# System.net
KiCad netlist of a schematic drawn in Altium Designer
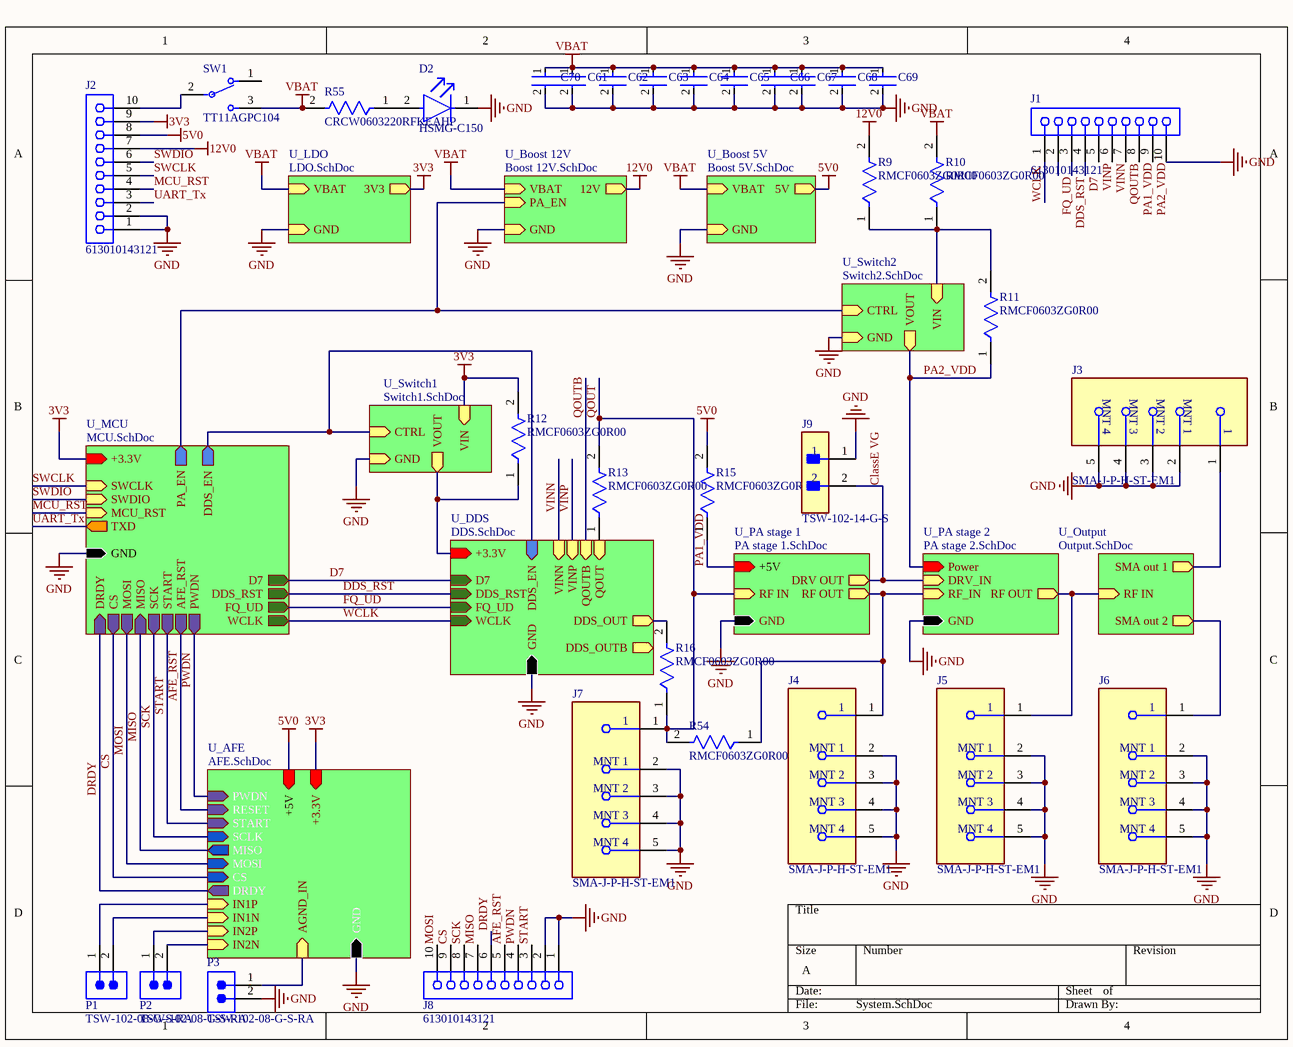
[diagram p0: System.SchDoc]

(export (version "E")
  (design (tool "Eeschema 10.0.6"))
  (components
    (comp (ref "C61")
      (value "GRM21BR60J107ME15K")
      (footprint "FP-GRM21B-0_2-e0_2_0_7-IPC_B")
      (description "Chip Multilayer Ceramic Capacitors for General Purpose, 0805, 100uF, X5R, 15%, 20%, 6.3V")
      (fields (field (name "TOLERANCE") "20%"))
      (libsource (lib "Altium Content Vault") (part "b4654b650e69147ec39a6b967a45e02"))
    )
    (comp (ref "C62")
      (value "GRM21BR60J107ME15K")
      (footprint "FP-GRM21B-0_2-e0_2_0_7-IPC_B")
      (description "Chip Multilayer Ceramic Capacitors for General Purpose, 0805, 100uF, X5R, 15%, 20%, 6.3V")
      (fields (field (name "TOLERANCE") "20%"))
      (libsource (lib "Altium Content Vault") (part "b4654b650e69147ec39a6b967a45e02"))
    )
    (comp (ref "C63")
      (value "GRM21BR60J107ME15K")
      (footprint "FP-GRM21B-0_2-e0_2_0_7-IPC_B")
      (description "Chip Multilayer Ceramic Capacitors for General Purpose, 0805, 100uF, X5R, 15%, 20%, 6.3V")
      (fields (field (name "TOLERANCE") "20%"))
      (libsource (lib "Altium Content Vault") (part "b4654b650e69147ec39a6b967a45e02"))
    )
    (comp (ref "C64")
      (value "GRM21BR60J107ME15K")
      (footprint "FP-GRM21B-0_2-e0_2_0_7-IPC_B")
      (description "Chip Multilayer Ceramic Capacitors for General Purpose, 0805, 100uF, X5R, 15%, 20%, 6.3V")
      (fields (field (name "TOLERANCE") "20%"))
      (libsource (lib "Altium Content Vault") (part "b4654b650e69147ec39a6b967a45e02"))
    )
    (comp (ref "C65")
      (value "GRM21BR60J107ME15K")
      (footprint "FP-GRM21B-0_2-e0_2_0_7-IPC_B")
      (description "Chip Multilayer Ceramic Capacitors for General Purpose, 0805, 100uF, X5R, 15%, 20%, 6.3V")
      (fields (field (name "TOLERANCE") "20%"))
      (libsource (lib "Altium Content Vault") (part "b4654b650e69147ec39a6b967a45e02"))
    )
    (comp (ref "C66")
      (value "GRM21BR60J107ME15K")
      (footprint "FP-GRM21B-0_2-e0_2_0_7-IPC_B")
      (description "Chip Multilayer Ceramic Capacitors for General Purpose, 0805, 100uF, X5R, 15%, 20%, 6.3V")
      (fields (field (name "TOLERANCE") "20%"))
      (libsource (lib "Altium Content Vault") (part "b4654b650e69147ec39a6b967a45e02"))
    )
    (comp (ref "C67")
      (value "GRM21BR60J107ME15K")
      (footprint "FP-GRM21B-0_2-e0_2_0_7-IPC_B")
      (description "Chip Multilayer Ceramic Capacitors for General Purpose, 0805, 100uF, X5R, 15%, 20%, 6.3V")
      (fields (field (name "TOLERANCE") "20%"))
      (libsource (lib "Altium Content Vault") (part "b4654b650e69147ec39a6b967a45e02"))
    )
    (comp (ref "C68")
      (value "GRM21BR60J107ME15K")
      (footprint "FP-GRM21B-0_2-e0_2_0_7-IPC_B")
      (description "Chip Multilayer Ceramic Capacitors for General Purpose, 0805, 100uF, X5R, 15%, 20%, 6.3V")
      (fields (field (name "TOLERANCE") "20%"))
      (libsource (lib "Altium Content Vault") (part "b4654b650e69147ec39a6b967a45e02"))
    )
    (comp (ref "C69")
      (value "GRM21BR60J107ME15K")
      (footprint "FP-GRM21B-0_2-e0_2_0_7-IPC_B")
      (description "Chip Multilayer Ceramic Capacitors for General Purpose, 0805, 100uF, X5R, 15%, 20%, 6.3V")
      (fields (field (name "TOLERANCE") "20%"))
      (libsource (lib "Altium Content Vault") (part "b4654b650e69147ec39a6b967a45e02"))
    )
    (comp (ref "C70")
      (value "GRM21BR60J107ME15K")
      (footprint "FP-GRM21B-0_2-e0_2_0_7-IPC_B")
      (description "Chip Multilayer Ceramic Capacitors for General Purpose, 0805, 100uF, X5R, 15%, 20%, 6.3V")
      (fields (field (name "TOLERANCE") "20%"))
      (libsource (lib "Altium Content Vault") (part "b4654b650e69147ec39a6b967a45e02"))
    )
    (comp (ref "D2")
      (value "HSMG-C150")
      (footprint "FP-HSMG-C150-MFG")
      (description "LED GREEN DIFFUSED 1206 SMD")
      (fields
        (field (name "MANUFACTURER") "Broadcom")
        (field (name "OCTOPART") "https://octopart.com/hsmg-c150-broadcom-71131304")
      )
      (libsource (lib "Altium Content Vault") (part "8706943c75ba83719d021d2fdc84c58"))
    )
    (comp (ref "J1")
      (value "613010143121")
      (footprint "613010143121")
      (libsource (lib "Altium Content Vault") (part "Header_Female_1R_10P"))
    )
    (comp (ref "J2")
      (value "613010143121")
      (footprint "613010143121")
      (libsource (lib "Altium Content Vault") (part "Header_Female_1R_10P"))
    )
    (comp (ref "J3")
      (value "SMA-J-P-H-ST-EM1")
      (footprint "FP-SMA-J-P-H-ST-EM1-MFG")
      (description "CONN SMA JACK STR 50OHM EDGE MNT")
      (libsource (lib "") (part "c65b8a639cdaef1819ea20b5466f8fa_1"))
    )
    (comp (ref "J4")
      (value "SMA-J-P-H-ST-EM1")
      (footprint "FP-SMA-J-P-H-ST-EM1-MFG")
      (description "CONN SMA JACK STR 50OHM EDGE MNT")
      (libsource (lib "Altium Content Vault") (part "c65b8a639cdaef1819ea20b5466f8fa"))
    )
    (comp (ref "J5")
      (value "SMA-J-P-H-ST-EM1")
      (footprint "FP-SMA-J-P-H-ST-EM1-MFG")
      (description "CONN SMA JACK STR 50OHM EDGE MNT")
      (libsource (lib "Altium Content Vault") (part "c65b8a639cdaef1819ea20b5466f8fa"))
    )
    (comp (ref "J6")
      (value "SMA-J-P-H-ST-EM1")
      (footprint "FP-SMA-J-P-H-ST-EM1-MFG")
      (description "CONN SMA JACK STR 50OHM EDGE MNT")
      (libsource (lib "Altium Content Vault") (part "c65b8a639cdaef1819ea20b5466f8fa"))
    )
    (comp (ref "J7")
      (value "SMA-J-P-H-ST-EM1")
      (footprint "FP-SMA-J-P-H-ST-EM1-MFG")
      (description "CONN SMA JACK STR 50OHM EDGE MNT")
      (libsource (lib "Altium Content Vault") (part "c65b8a639cdaef1819ea20b5466f8fa"))
    )
    (comp (ref "J8")
      (value "613010143121")
      (footprint "613010143121")
      (libsource (lib "Altium Content Vault") (part "Header_Female_1R_10P"))
    )
    (comp (ref "J9")
      (value "TSW-102-14-G-S")
      (footprint "FP-TSW-102-14-G-S-MFG")
      (description "CONN HEADER VERT 2POS 2.54MM")
      (libsource (lib "Altium Content Vault") (part "88c1139f9d239099ffebecbe3f7647a"))
    )
    (comp (ref "P1")
      (value "TSW-102-08-G-S-RA")
      (footprint "SMTC-TSW-102-08-X-S-RA")
      (fields (field (name "MANUFACTURER") "Samtec"))
      (libsource (lib "Altium Content Vault") (part "SMTC-TSW-102-X-X-S-X"))
    )
    (comp (ref "P2")
      (value "TSW-102-08-G-S-RA")
      (footprint "SMTC-TSW-102-08-X-S-RA")
      (fields (field (name "MANUFACTURER") "Samtec"))
      (libsource (lib "Altium Content Vault") (part "SMTC-TSW-102-X-X-S-X"))
    )
    (comp (ref "P3")
      (value "TSW-102-08-G-S-RA")
      (footprint "SMTC-TSW-102-08-X-S-RA")
      (fields (field (name "MANUFACTURER") "Samtec"))
      (libsource (lib "Altium Content Vault") (part "SMTC-TSW-102-X-X-S-X"))
    )
    (comp (ref "R9")
      (value "RMCF0603ZG0R00")
      (footprint "FP-RMCF0603-IPC_B")
      (description "0Ω ±0 0.1W 0603 Thick Film Chip Resistor AEC-Q200 compliant")
      (libsource (lib "Altium Content Vault") (part "1029c3af85768c4190bb7ad29bc67b5"))
    )
    (comp (ref "R10")
      (value "RMCF0603ZG0R00")
      (footprint "FP-RMCF0603-IPC_B")
      (description "0Ω ±0 0.1W 0603 Thick Film Chip Resistor AEC-Q200 compliant")
      (libsource (lib "Altium Content Vault") (part "1029c3af85768c4190bb7ad29bc67b5"))
    )
    (comp (ref "R11")
      (value "RMCF0603ZG0R00")
      (footprint "FP-RMCF0603-IPC_B")
      (description "0Ω ±0 0.1W 0603 Thick Film Chip Resistor AEC-Q200 compliant")
      (libsource (lib "Altium Content Vault") (part "1029c3af85768c4190bb7ad29bc67b5"))
    )
    (comp (ref "R12")
      (value "RMCF0603ZG0R00")
      (footprint "FP-RMCF0603-IPC_B")
      (description "0Ω ±0 0.1W 0603 Thick Film Chip Resistor AEC-Q200 compliant")
      (libsource (lib "Altium Content Vault") (part "1029c3af85768c4190bb7ad29bc67b5"))
    )
    (comp (ref "R13")
      (value "RMCF0603ZG0R00")
      (footprint "FP-RMCF0603-IPC_B")
      (description "0Ω ±0 0.1W 0603 Thick Film Chip Resistor AEC-Q200 compliant")
      (libsource (lib "Altium Content Vault") (part "1029c3af85768c4190bb7ad29bc67b5"))
    )
    (comp (ref "R15")
      (value "RMCF0603ZG0R00")
      (footprint "FP-RMCF0603-IPC_B")
      (description "0Ω ±0 0.1W 0603 Thick Film Chip Resistor AEC-Q200 compliant")
      (libsource (lib "Altium Content Vault") (part "1029c3af85768c4190bb7ad29bc67b5"))
    )
    (comp (ref "R16")
      (value "RMCF0603ZG0R00")
      (footprint "FP-RMCF0603-IPC_B")
      (description "0Ω ±0 0.1W 0603 Thick Film Chip Resistor AEC-Q200 compliant")
      (libsource (lib "Altium Content Vault") (part "1029c3af85768c4190bb7ad29bc67b5"))
    )
    (comp (ref "R54")
      (value "RMCF0603ZG0R00")
      (footprint "FP-RMCF0603-IPC_B")
      (description "0Ω ±0 0.1W 0603 Thick Film Chip Resistor AEC-Q200 compliant")
      (libsource (lib "Altium Content Vault") (part "1029c3af85768c4190bb7ad29bc67b5"))
    )
    (comp (ref "R55")
      (value "CRCW0603220RFKEAHP")
      (footprint "FP-CRCW0603-HPe3-IPC_A")
      (description "RES Thick Film, 220Ω, 1%, 0.33W, 100ppm/°C, 0603")
      (fields (field (name "TOLERANCE") "1%"))
      (libsource (lib "Altium Content Vault") (part "1029c3af85768c4190bb7ad29bc67b5"))
    )
    (comp (ref "SW1")
      (value "TT11AGPC104")
      (footprint "FP-TT11AGPC104-MFG")
      (description "SWITCH TOGGLE SPST 0.4VA 20V")
      (libsource (lib "Altium Content Vault") (part "52c419afdc2a387c7d548259a9aeefb"))
    )
  )
  (nets
    (net (code "1") (name "/AFE_RST") (class "Default")
      (node (ref "J8") (pin "5") (pinfunction "5_5") (pintype "passive"))
    )
    (net (code "2") (name "/AGND_IN") (class "Default")
      (node (ref "P3") (pin "1") (pinfunction "1_1") (pintype "passive"))
    )
    (net (code "3") (name "/CS") (class "Default")
      (node (ref "J8") (pin "9") (pinfunction "9_9") (pintype "passive"))
    )
    (net (code "4") (name "/ClassE VG") (class "Default")
      (node (ref "J9") (pin "2") (pinfunction "2_2") (pintype "passive"))
    )
    (net (code "5") (name "/D7") (class "Default")
      (node (ref "J1") (pin "4") (pinfunction "4_4") (pintype "passive"))
    )
    (net (code "7") (name "/DDS_OUT") (class "Default")
      (node (ref "R16") (pin "2") (pinfunction "2_2") (pintype "passive"))
    )
    (net (code "9") (name "/DDS_RST") (class "Default")
      (node (ref "J1") (pin "3") (pinfunction "3_3") (pintype "passive"))
    )
    (net (code "10") (name "/DRDY") (class "Default")
      (node (ref "J8") (pin "6") (pinfunction "6_6") (pintype "passive"))
    )
    (net (code "11") (name "/FQ_UD") (class "Default")
      (node (ref "J1") (pin "2") (pinfunction "2_2") (pintype "passive"))
    )
    (net (code "12") (name "/IN1N") (class "Default")
      (node (ref "P1") (pin "2") (pinfunction "2_2") (pintype "passive"))
    )
    (net (code "13") (name "/IN1P") (class "Default")
      (node (ref "P1") (pin "1") (pinfunction "1_1") (pintype "passive"))
    )
    (net (code "14") (name "/IN2N") (class "Default")
      (node (ref "P2") (pin "2") (pinfunction "2_2") (pintype "passive"))
    )
    (net (code "15") (name "/IN2P") (class "Default")
      (node (ref "P2") (pin "1") (pinfunction "1_1") (pintype "passive"))
    )
    (net (code "16") (name "/MCU_RST") (class "Default")
      (node (ref "J2") (pin "4") (pinfunction "4_4") (pintype "passive"))
    )
    (net (code "17") (name "/MISO") (class "Default")
      (node (ref "J8") (pin "7") (pinfunction "7_7") (pintype "passive"))
    )
    (net (code "18") (name "/MOSI") (class "Default")
      (node (ref "J8") (pin "10") (pinfunction "10_10") (pintype "passive"))
    )
    (net (code "19") (name "/PA1_VDD") (class "Default")
      (node (ref "J1") (pin "8") (pinfunction "8_8") (pintype "passive"))
      (node (ref "R15") (pin "1") (pinfunction "1_1") (pintype "passive"))
    )
    (net (code "20") (name "/PA2_VDD") (class "Default")
      (node (ref "J1") (pin "9") (pinfunction "9_9") (pintype "passive"))
      (node (ref "R11") (pin "1") (pinfunction "1_1") (pintype "passive"))
    )
    (net (code "22") (name "/PWDN") (class "Default")
      (node (ref "J8") (pin "4") (pinfunction "4_4") (pintype "passive"))
    )
    (net (code "23") (name "/QOUT") (class "Default")
      (node (ref "J7") (pin "1") (pinfunction "1_1") (pintype "passive"))
      (node (ref "R13") (pin "2") (pinfunction "2_2") (pintype "passive"))
      (node (ref "R16") (pin "1") (pinfunction "1_1") (pintype "passive"))
      (node (ref "R54") (pin "2") (pinfunction "2_2") (pintype "passive"))
    )
    (net (code "24") (name "/QOUTB") (class "Default")
      (node (ref "J1") (pin "7") (pinfunction "7_7") (pintype "passive"))
    )
    (net (code "25") (name "/QOUT_1") (class "Default")
      (node (ref "R13") (pin "1") (pinfunction "1_1") (pintype "passive"))
    )
    (net (code "26") (name "/RF OUT") (class "Default")
      (node (ref "J5") (pin "1") (pinfunction "1_1") (pintype "passive"))
    )
    (net (code "27") (name "/RF OUT_1") (class "Default")
      (node (ref "J4") (pin "1") (pinfunction "1_1") (pintype "passive"))
      (node (ref "R54") (pin "1") (pinfunction "1_1") (pintype "passive"))
    )
    (net (code "28") (name "/SCK") (class "Default")
      (node (ref "J8") (pin "8") (pinfunction "8_8") (pintype "passive"))
    )
    (net (code "29") (name "/SMA out 1") (class "Default")
      (node (ref "J3") (pin "1") (pinfunction "1_1") (pintype "passive"))
    )
    (net (code "30") (name "/SMA out 2") (class "Default")
      (node (ref "J6") (pin "1") (pinfunction "1_1") (pintype "passive"))
    )
    (net (code "31") (name "/START") (class "Default")
      (node (ref "J8") (pin "3") (pinfunction "3_3") (pintype "passive"))
    )
    (net (code "32") (name "/SWCLK") (class "Default")
      (node (ref "J2") (pin "5") (pinfunction "5_5") (pintype "passive"))
    )
    (net (code "33") (name "/SWDIO") (class "Default")
      (node (ref "J2") (pin "6") (pinfunction "6_6") (pintype "passive"))
    )
    (net (code "34") (name "/UART_Tx") (class "Default")
      (node (ref "J2") (pin "3") (pinfunction "3_3") (pintype "passive"))
    )
    (net (code "35") (name "/VIN") (class "Default")
      (node (ref "R10") (pin "1") (pinfunction "1_1") (pintype "passive"))
      (node (ref "R11") (pin "2") (pinfunction "2_2") (pintype "passive"))
      (node (ref "R9") (pin "1") (pinfunction "1_1") (pintype "passive"))
    )
    (net (code "36") (name "/VINN") (class "Default")
      (node (ref "J1") (pin "6") (pinfunction "6_6") (pintype "passive"))
    )
    (net (code "37") (name "/VINP") (class "Default")
      (node (ref "J1") (pin "5") (pinfunction "5_5") (pintype "passive"))
    )
    (net (code "38") (name "/VOUT") (class "Default")
      (node (ref "R12") (pin "1") (pinfunction "1_1") (pintype "passive"))
    )
    (net (code "39") (name "/WCLK") (class "Default")
      (node (ref "J1") (pin "1") (pinfunction "1_1") (pintype "passive"))
    )
    (net (code "40") (name "3V3") (class "Default")
      (node (ref "J2") (pin "9") (pinfunction "9_9") (pintype "passive"))
      (node (ref "R12") (pin "2") (pinfunction "2_2") (pintype "passive"))
    )
    (net (code "41") (name "5V0") (class "Default")
      (node (ref "J2") (pin "8") (pinfunction "8_8") (pintype "passive"))
      (node (ref "R15") (pin "2") (pinfunction "2_2") (pintype "passive"))
    )
    (net (code "42") (name "12V0") (class "Default")
      (node (ref "J2") (pin "7") (pinfunction "7_7") (pintype "passive"))
      (node (ref "R9") (pin "2") (pinfunction "2_2") (pintype "passive"))
    )
    (net (code "43") (name "GND") (class "Default")
      (node (ref "C61") (pin "2") (pinfunction "2_2") (pintype "passive"))
      (node (ref "C62") (pin "2") (pinfunction "2_2") (pintype "passive"))
      (node (ref "C63") (pin "2") (pinfunction "2_2") (pintype "passive"))
      (node (ref "C64") (pin "2") (pinfunction "2_2") (pintype "passive"))
      (node (ref "C65") (pin "2") (pinfunction "2_2") (pintype "passive"))
      (node (ref "C66") (pin "2") (pinfunction "2_2") (pintype "passive"))
      (node (ref "C67") (pin "2") (pinfunction "2_2") (pintype "passive"))
      (node (ref "C68") (pin "2") (pinfunction "2_2") (pintype "passive"))
      (node (ref "C69") (pin "2") (pinfunction "2_2") (pintype "passive"))
      (node (ref "C70") (pin "2") (pinfunction "2_2") (pintype "passive"))
      (node (ref "D2") (pin "1") (pinfunction "C_1") (pintype "passive"))
      (node (ref "J1") (pin "10") (pinfunction "10_10") (pintype "passive"))
      (node (ref "J2") (pin "1") (pinfunction "1_1") (pintype "passive"))
      (node (ref "J2") (pin "2") (pinfunction "2_2") (pintype "passive"))
      (node (ref "J3") (pin "2") (pinfunction "MNT_1_2") (pintype "passive"))
      (node (ref "J3") (pin "3") (pinfunction "MNT_2_3") (pintype "passive"))
      (node (ref "J3") (pin "4") (pinfunction "MNT_3_4") (pintype "passive"))
      (node (ref "J3") (pin "5") (pinfunction "MNT_4_5") (pintype "passive"))
      (node (ref "J4") (pin "2") (pinfunction "MNT_1_2") (pintype "passive"))
      (node (ref "J4") (pin "3") (pinfunction "MNT_2_3") (pintype "passive"))
      (node (ref "J4") (pin "4") (pinfunction "MNT_3_4") (pintype "passive"))
      (node (ref "J4") (pin "5") (pinfunction "MNT_4_5") (pintype "passive"))
      (node (ref "J5") (pin "2") (pinfunction "MNT_1_2") (pintype "passive"))
      (node (ref "J5") (pin "3") (pinfunction "MNT_2_3") (pintype "passive"))
      (node (ref "J5") (pin "4") (pinfunction "MNT_3_4") (pintype "passive"))
      (node (ref "J5") (pin "5") (pinfunction "MNT_4_5") (pintype "passive"))
      (node (ref "J6") (pin "2") (pinfunction "MNT_1_2") (pintype "passive"))
      (node (ref "J6") (pin "3") (pinfunction "MNT_2_3") (pintype "passive"))
      (node (ref "J6") (pin "4") (pinfunction "MNT_3_4") (pintype "passive"))
      (node (ref "J6") (pin "5") (pinfunction "MNT_4_5") (pintype "passive"))
      (node (ref "J7") (pin "2") (pinfunction "MNT_1_2") (pintype "passive"))
      (node (ref "J7") (pin "3") (pinfunction "MNT_2_3") (pintype "passive"))
      (node (ref "J7") (pin "4") (pinfunction "MNT_3_4") (pintype "passive"))
      (node (ref "J7") (pin "5") (pinfunction "MNT_4_5") (pintype "passive"))
      (node (ref "J8") (pin "1") (pinfunction "1_1") (pintype "passive"))
      (node (ref "J8") (pin "2") (pinfunction "2_2") (pintype "passive"))
      (node (ref "J9") (pin "1") (pinfunction "1_1") (pintype "passive"))
      (node (ref "P3") (pin "2") (pinfunction "2_2") (pintype "passive"))
    )
    (net (code "44") (name "Net-(D2-A)") (class "Default")
      (node (ref "D2") (pin "2") (pinfunction "A_2") (pintype "passive"))
      (node (ref "R55") (pin "1") (pinfunction "1_1") (pintype "passive"))
    )
    (net (code "45") (name "Net-(J2-Pad10)") (class "Default")
      (node (ref "J2") (pin "10") (pinfunction "10_10") (pintype "passive"))
      (node (ref "SW1") (pin "2") (pinfunction "2_2") (pintype "passive"))
    )
    (net (code "46") (name "VBAT") (class "Default")
      (node (ref "C61") (pin "1") (pinfunction "1_1") (pintype "passive"))
      (node (ref "C62") (pin "1") (pinfunction "1_1") (pintype "passive"))
      (node (ref "C63") (pin "1") (pinfunction "1_1") (pintype "passive"))
      (node (ref "C64") (pin "1") (pinfunction "1_1") (pintype "passive"))
      (node (ref "C65") (pin "1") (pinfunction "1_1") (pintype "passive"))
      (node (ref "C66") (pin "1") (pinfunction "1_1") (pintype "passive"))
      (node (ref "C67") (pin "1") (pinfunction "1_1") (pintype "passive"))
      (node (ref "C68") (pin "1") (pinfunction "1_1") (pintype "passive"))
      (node (ref "C69") (pin "1") (pinfunction "1_1") (pintype "passive"))
      (node (ref "C70") (pin "1") (pinfunction "1_1") (pintype "passive"))
      (node (ref "R10") (pin "2") (pinfunction "2_2") (pintype "passive"))
      (node (ref "R55") (pin "2") (pinfunction "2_2") (pintype "passive"))
      (node (ref "SW1") (pin "3") (pinfunction "3_3") (pintype "passive"))
    )
    (net (code "47") (name "unconnected-(SW1-Pad1)") (class "Default")
      (node (ref "SW1") (pin "1") (pinfunction "1_1") (pintype "passive"))
    )
  )
)
